# MCU.net
KiCad netlist of a schematic drawn in Altium Designer
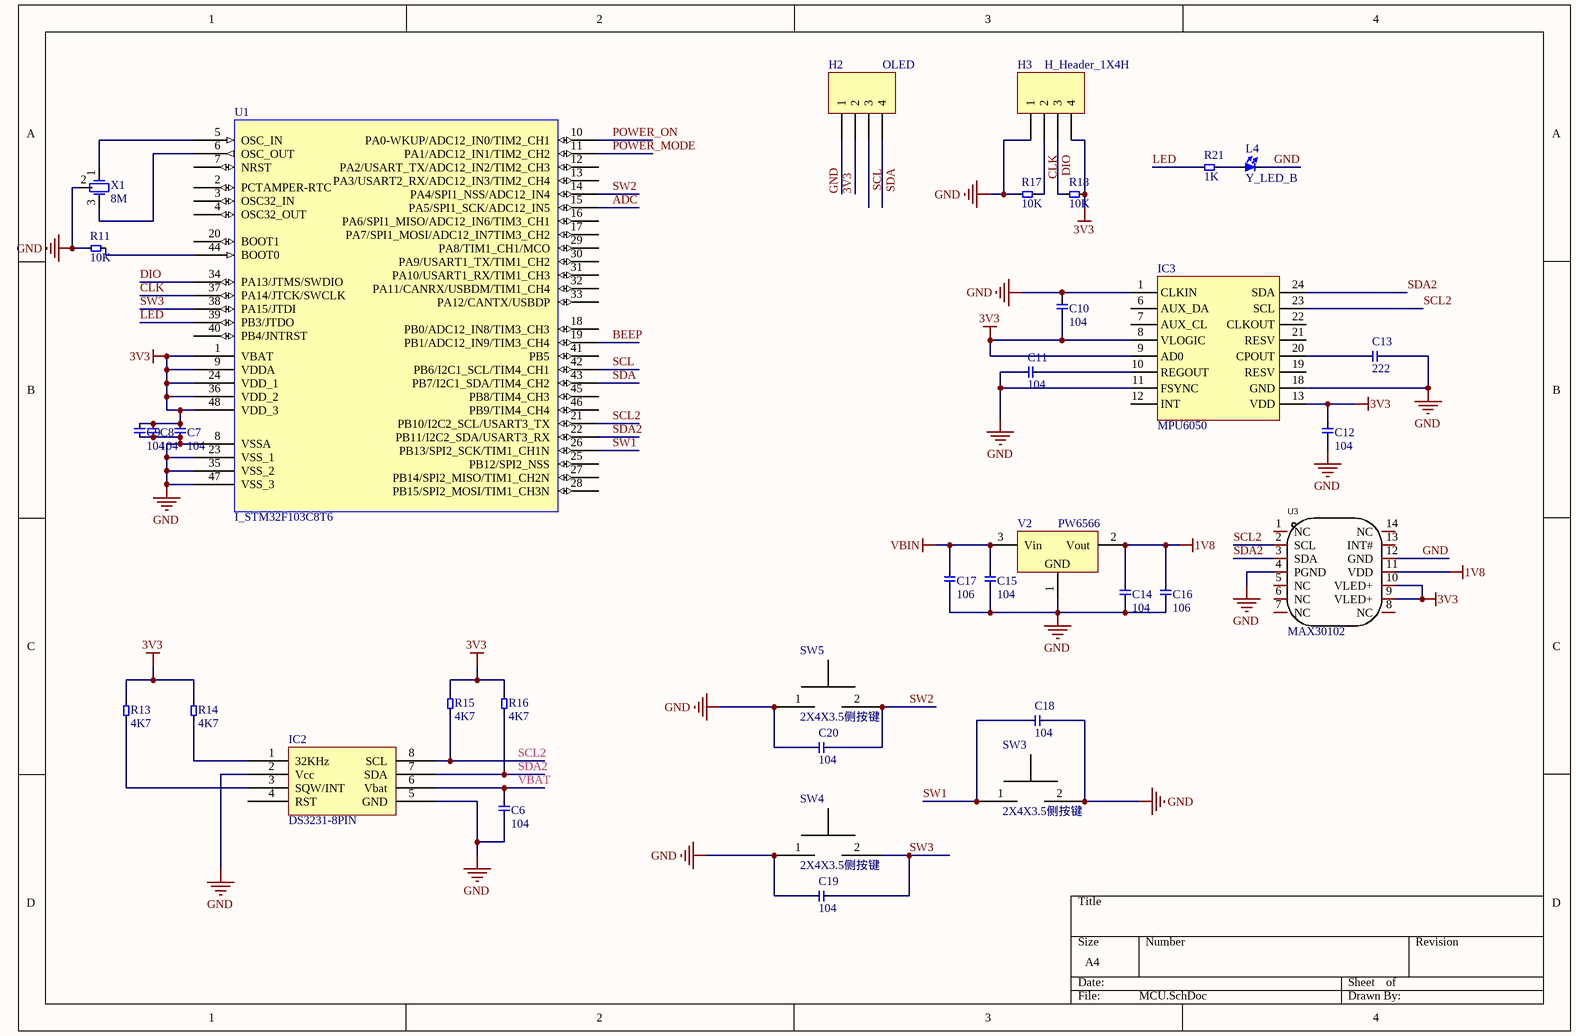
[diagram p0: MCU.SchDoc]

(export (version "E")
  (design (tool "Eeschema 10.0.6"))
  (components
    (comp (ref "C6")
      (value "104")
      (footprint "C_0603")
      (description "无极性贴片电容")
      (libsource (lib "电阻电容电感库") (part "C_无极贴片"))
    )
    (comp (ref "C7")
      (value "104")
      (footprint "C_0603")
      (description "无极性贴片电容")
      (libsource (lib "电阻电容电感库") (part "C_无极贴片"))
    )
    (comp (ref "C8")
      (value "104")
      (footprint "C_0603")
      (description "无极性贴片电容")
      (libsource (lib "电阻电容电感库") (part "C_无极贴片"))
    )
    (comp (ref "C9")
      (value "104")
      (footprint "C_0603")
      (description "无极性贴片电容")
      (libsource (lib "电阻电容电感库") (part "C_无极贴片"))
    )
    (comp (ref "C10")
      (value "104")
      (footprint "C_0603")
      (description "无极性贴片电容")
      (libsource (lib "电阻电容电感库") (part "C_无极贴片"))
    )
    (comp (ref "C11")
      (value "104")
      (footprint "C_0603")
      (description "无极性贴片电容")
      (libsource (lib "电阻电容电感库") (part "C_无极贴片"))
    )
    (comp (ref "C12")
      (value "104")
      (footprint "C_0603")
      (description "无极性贴片电容")
      (libsource (lib "电阻电容电感库") (part "C_无极贴片"))
    )
    (comp (ref "C13")
      (value "222")
      (footprint "C_0603")
      (description "无极性贴片电容")
      (libsource (lib "电阻电容电感库") (part "C_无极贴片"))
    )
    (comp (ref "C14")
      (value "104")
      (footprint "C_0603")
      (description "无极性贴片电容")
      (libsource (lib "电阻电容电感库") (part "C_无极贴片"))
    )
    (comp (ref "C15")
      (value "104")
      (footprint "C_0603")
      (description "无极性贴片电容")
      (libsource (lib "电阻电容电感库") (part "C_无极贴片"))
    )
    (comp (ref "C16")
      (value "106")
      (footprint "C_0603")
      (description "无极性贴片电容")
      (libsource (lib "电阻电容电感库") (part "C_无极贴片"))
    )
    (comp (ref "C17")
      (value "106")
      (footprint "C_0603")
      (description "无极性贴片电容")
      (libsource (lib "电阻电容电感库") (part "C_无极贴片"))
    )
    (comp (ref "C18")
      (value "104")
      (footprint "C_0603")
      (description "无极性贴片电容")
      (libsource (lib "电阻电容电感库") (part "C_无极贴片"))
    )
    (comp (ref "C19")
      (value "104")
      (footprint "C_0603")
      (description "无极性贴片电容")
      (libsource (lib "电阻电容电感库") (part "C_无极贴片"))
    )
    (comp (ref "C20")
      (value "104")
      (footprint "C_0603")
      (description "无极性贴片电容")
      (libsource (lib "电阻电容电感库") (part "C_无极贴片"))
    )
    (comp (ref "H2")
      (value "OLED")
      (footprint "H_Header_1X4")
      (description "单排4针排母")
      (fields (field (name "PUBLISHER") "Altium Limited"))
      (libsource (lib "接插件") (part "H_Header_1X4H"))
    )
    (comp (ref "H3")
      (value "H_Header_1X4H")
      (footprint "H_Header_1X4")
      (description "单排4针排母")
      (fields (field (name "PUBLISHER") "Altium Limited"))
      (libsource (lib "接插件") (part "H_Header_1X4H"))
    )
    (comp (ref "IC2")
      (value "DS3231-8PIN")
      (footprint "SOP8_N")
      (libsource (lib "我的元件") (part "DS3231-8PIN"))
    )
    (comp (ref "IC3")
      (value "MPU6050")
      (footprint "QFN24 4x4_M")
      (description "陀螺仪")
      (libsource (lib "我的元件") (part "MPU6050"))
    )
    (comp (ref "L4")
      (value "Y_LED_B")
      (footprint "Y_LED_0603_B")
      (description "蓝色LED")
      (libsource (lib "声光元件") (part "Y_LED_B"))
    )
    (comp (ref "R11")
      (value "10K")
      (footprint "R_0603")
      (description "贴片电阻")
      (libsource (lib "电阻电容电感库") (part "R_贴片"))
    )
    (comp (ref "R13")
      (value "4K7")
      (footprint "R_0603")
      (description "贴片电阻")
      (libsource (lib "电阻电容电感库") (part "R_贴片"))
    )
    (comp (ref "R14")
      (value "4K7")
      (footprint "R_0603")
      (description "贴片电阻")
      (libsource (lib "电阻电容电感库") (part "R_贴片"))
    )
    (comp (ref "R15")
      (value "4K7")
      (footprint "R_0603")
      (description "贴片电阻")
      (libsource (lib "电阻电容电感库") (part "R_贴片"))
    )
    (comp (ref "R16")
      (value "4K7")
      (footprint "R_0603")
      (description "贴片电阻")
      (libsource (lib "电阻电容电感库") (part "R_贴片"))
    )
    (comp (ref "R17")
      (value "10K")
      (footprint "R_0603")
      (description "贴片电阻")
      (libsource (lib "电阻电容电感库") (part "R_贴片"))
    )
    (comp (ref "R18")
      (value "10K")
      (footprint "R_0603")
      (description "贴片电阻")
      (libsource (lib "电阻电容电感库") (part "R_贴片"))
    )
    (comp (ref "R21")
      (value "1K")
      (footprint "R_0603")
      (description "贴片电阻")
      (libsource (lib "电阻电容电感库") (part "R_贴片"))
    )
    (comp (ref "SW3")
      (value "2X4X3.5侧按键")
      (footprint "2X4X3.5贴片侧按开关")
      (libsource (lib "MyWatch") (part "2X4X3.5侧按键"))
    )
    (comp (ref "SW4")
      (value "2X4X3.5侧按键")
      (footprint "2X4X3.5贴片侧按开关")
      (libsource (lib "MyWatch") (part "2X4X3.5侧按键"))
    )
    (comp (ref "SW5")
      (value "2X4X3.5侧按键")
      (footprint "2X4X3.5贴片侧按开关")
      (libsource (lib "MyWatch") (part "2X4X3.5侧按键"))
    )
    (comp (ref "U1")
      (value "I_STM32F103C8T6")
      (footprint "I_LQFP-48")
      (description "LQFP-48")
      (libsource (lib "集成器件") (part "I_STM32F103C8T6"))
    )
    (comp (ref "U3")
      (value "MAX30102")
      (footprint "OESIP-14_L5.6-W3.3-P0.80-TL")
      (fields (field (name "MANUFACTURER") "MAXIM(美信)") (field (name "MANUFACTURER PART") "MAX30101EFD+T"))
      (libsource (lib "MAX30102") (part "MAX30101EFD+T"))
    )
    (comp (ref "V2")
      (value "PW6566")
      (footprint "SOT23-3N")
      (description "低压差线性稳压芯片")
      (fields (field (name "版权归属") "源创客"))
      (libsource (lib "MyWatch") (part "XC6206P332MR"))
    )
    (comp (ref "X1")
      (value "8M")
      (footprint "XTAL-3.2*1.3MM")
      (description "8~20M-3.2*1.3mm-3P")
      (libsource (lib "物流小车-pcb-树莓派") (part "XTAL-3213-3P"))
    )
  )
  (nets
    (net (code "1") (name "/ADC") (class "Default")
      (node (ref "U1") (pin "15") (pinfunction "PA5/SPI1_SCK/ADC12_IN5_15") (pintype "bidirectional"))
    )
    (net (code "2") (name "/BEEP") (class "Default")
      (node (ref "U1") (pin "19") (pinfunction "PB1/ADC12_IN9/TIM3_CH4_19") (pintype "bidirectional"))
    )
    (net (code "3") (name "/CLK") (class "Default")
      (node (ref "H3") (pin "2") (pinfunction "2_2") (pintype "passive"))
      (node (ref "R17") (pin "2") (pintype "passive"))
      (node (ref "U1") (pin "37") (pinfunction "PA14/JTCK/SWCLK_37") (pintype "bidirectional"))
    )
    (net (code "4") (name "/DIO") (class "Default")
      (node (ref "H3") (pin "3") (pinfunction "3_3") (pintype "passive"))
      (node (ref "R18") (pin "1") (pintype "passive"))
      (node (ref "U1") (pin "34") (pinfunction "PA13/JTMS/SWDIO_34") (pintype "bidirectional"))
    )
    (net (code "5") (name "/LED") (class "Default")
      (node (ref "R21") (pin "2") (pintype "passive"))
      (node (ref "U1") (pin "39") (pinfunction "PB3/JTDO_39") (pintype "bidirectional"))
    )
    (net (code "6") (name "/POWER_MODE") (class "Default")
      (node (ref "U1") (pin "11") (pinfunction "PA1/ADC12_IN1/TIM2_CH2_11") (pintype "bidirectional"))
    )
    (net (code "7") (name "/POWER_ON") (class "Default")
      (node (ref "U1") (pin "10") (pinfunction "PA0-WKUP/ADC12_IN0/TIM2_CH1_10") (pintype "bidirectional"))
    )
    (net (code "8") (name "/SCL") (class "Default")
      (node (ref "H2") (pin "3") (pinfunction "3_3") (pintype "passive"))
      (node (ref "U1") (pin "42") (pinfunction "PB6/I2C1_SCL/TIM4_CH1_42") (pintype "bidirectional"))
    )
    (net (code "9") (name "/SCL2") (class "Default")
      (node (ref "IC2") (pin "8") (pinfunction "SCL_8") (pintype "passive"))
      (node (ref "IC3") (pin "23") (pinfunction "SCL_23") (pintype "passive"))
      (node (ref "R15") (pin "1") (pintype "passive"))
      (node (ref "U1") (pin "21") (pinfunction "PB10/I2C2_SCL/USART3_TX_21") (pintype "bidirectional"))
      (node (ref "U3") (pin "2") (pinfunction "SCL_2") (pintype "passive"))
    )
    (net (code "10") (name "/SDA") (class "Default")
      (node (ref "H2") (pin "4") (pinfunction "4_4") (pintype "passive"))
      (node (ref "U1") (pin "43") (pinfunction "PB7/I2C1_SDA/TIM4_CH2_43") (pintype "bidirectional"))
    )
    (net (code "11") (name "/SDA2") (class "Default")
      (node (ref "IC2") (pin "7") (pinfunction "SDA_7") (pintype "passive"))
      (node (ref "IC3") (pin "24") (pinfunction "SDA_24") (pintype "passive"))
      (node (ref "R16") (pin "1") (pintype "passive"))
      (node (ref "U1") (pin "22") (pinfunction "PB11/I2C2_SDA/USART3_RX_22") (pintype "bidirectional"))
      (node (ref "U3") (pin "3") (pinfunction "SDA_3") (pintype "passive"))
    )
    (net (code "12") (name "/SW1") (class "Default")
      (node (ref "C18") (pin "1") (pinfunction "1_1") (pintype "passive"))
      (node (ref "SW3") (pin "1") (pinfunction "1_1") (pintype "passive"))
      (node (ref "U1") (pin "26") (pinfunction "PB13/SPI2_SCK/TIM1_CH1N_26") (pintype "bidirectional"))
    )
    (net (code "13") (name "/SW2") (class "Default")
      (node (ref "C20") (pin "2") (pinfunction "2_2") (pintype "passive"))
      (node (ref "SW5") (pin "2") (pinfunction "2_2") (pintype "passive"))
      (node (ref "U1") (pin "14") (pinfunction "PA4/SPI1_NSS/ADC12_IN4_14") (pintype "bidirectional"))
    )
    (net (code "14") (name "/SW3") (class "Default")
      (node (ref "C19") (pin "2") (pinfunction "2_2") (pintype "passive"))
      (node (ref "SW4") (pin "2") (pinfunction "2_2") (pintype "passive"))
      (node (ref "U1") (pin "38") (pinfunction "PA15/JTDI_38") (pintype "bidirectional"))
    )
    (net (code "15") (name "/VBAT") (class "Default")
      (node (ref "C6") (pin "2") (pinfunction "2_2") (pintype "passive"))
      (node (ref "IC2") (pin "6") (pinfunction "Vbat_6") (pintype "passive"))
    )
    (net (code "16") (name "1V8") (class "Default")
      (node (ref "C14") (pin "2") (pinfunction "2_2") (pintype "passive"))
      (node (ref "C16") (pin "2") (pinfunction "2_2") (pintype "passive"))
      (node (ref "U3") (pin "11") (pinfunction "VDD_11") (pintype "passive"))
      (node (ref "V2") (pin "2") (pinfunction "Vout_2") (pintype "passive"))
    )
    (net (code "17") (name "3V3") (class "Default")
      (node (ref "C10") (pin "1") (pinfunction "1_1") (pintype "passive"))
      (node (ref "C12") (pin "1") (pinfunction "1_1") (pintype "passive"))
      (node (ref "C7") (pin "2") (pinfunction "2_2") (pintype "passive"))
      (node (ref "C8") (pin "2") (pinfunction "2_2") (pintype "passive"))
      (node (ref "C9") (pin "2") (pinfunction "2_2") (pintype "passive"))
      (node (ref "H2") (pin "2") (pinfunction "2_2") (pintype "passive"))
      (node (ref "H3") (pin "4") (pinfunction "4_4") (pintype "passive"))
      (node (ref "IC3") (pin "13") (pinfunction "VDD_13") (pintype "passive"))
      (node (ref "IC3") (pin "8") (pinfunction "VLOGIC_8") (pintype "passive"))
      (node (ref "IC3") (pin "9") (pinfunction "AD0_9") (pintype "passive"))
      (node (ref "R13") (pin "2") (pintype "passive"))
      (node (ref "R14") (pin "2") (pintype "passive"))
      (node (ref "R15") (pin "2") (pintype "passive"))
      (node (ref "R16") (pin "2") (pintype "passive"))
      (node (ref "R18") (pin "2") (pintype "passive"))
      (node (ref "U1") (pin "1") (pinfunction "VBAT_1") (pintype "power_in"))
      (node (ref "U1") (pin "24") (pinfunction "VDD_1_24") (pintype "power_in"))
      (node (ref "U1") (pin "36") (pinfunction "VDD_2_36") (pintype "power_in"))
      (node (ref "U1") (pin "48") (pinfunction "VDD_3_48") (pintype "power_in"))
      (node (ref "U1") (pin "9") (pinfunction "VDDA_9") (pintype "power_in"))
      (node (ref "U3") (pin "10") (pinfunction "VLED+_10") (pintype "passive"))
      (node (ref "U3") (pin "9") (pinfunction "VLED+_9") (pintype "passive"))
    )
    (net (code "18") (name "GND") (class "Default")
      (node (ref "C10") (pin "2") (pinfunction "2_2") (pintype "passive"))
      (node (ref "C11") (pin "2") (pinfunction "2_2") (pintype "passive"))
      (node (ref "C12") (pin "2") (pinfunction "2_2") (pintype "passive"))
      (node (ref "C13") (pin "2") (pinfunction "2_2") (pintype "passive"))
      (node (ref "C14") (pin "1") (pinfunction "1_1") (pintype "passive"))
      (node (ref "C15") (pin "1") (pinfunction "1_1") (pintype "passive"))
      (node (ref "C16") (pin "1") (pinfunction "1_1") (pintype "passive"))
      (node (ref "C17") (pin "1") (pinfunction "1_1") (pintype "passive"))
      (node (ref "C18") (pin "2") (pinfunction "2_2") (pintype "passive"))
      (node (ref "C19") (pin "1") (pinfunction "1_1") (pintype "passive"))
      (node (ref "C20") (pin "1") (pinfunction "1_1") (pintype "passive"))
      (node (ref "C6") (pin "1") (pinfunction "1_1") (pintype "passive"))
      (node (ref "C7") (pin "1") (pinfunction "1_1") (pintype "passive"))
      (node (ref "C8") (pin "1") (pinfunction "1_1") (pintype "passive"))
      (node (ref "C9") (pin "1") (pinfunction "1_1") (pintype "passive"))
      (node (ref "H2") (pin "1") (pinfunction "1_1") (pintype "passive"))
      (node (ref "H3") (pin "1") (pinfunction "1_1") (pintype "passive"))
      (node (ref "IC2") (pin "2") (pinfunction "Vcc_2") (pintype "passive"))
      (node (ref "IC2") (pin "5") (pinfunction "GND_5") (pintype "passive"))
      (node (ref "IC3") (pin "1") (pinfunction "CLKIN_1") (pintype "passive"))
      (node (ref "IC3") (pin "11") (pinfunction "FSYNC_11") (pintype "passive"))
      (node (ref "IC3") (pin "18") (pinfunction "GND_18") (pintype "passive"))
      (node (ref "L4") (pin "2") (pintype "passive"))
      (node (ref "R11") (pin "1") (pintype "passive"))
      (node (ref "R17") (pin "1") (pintype "passive"))
      (node (ref "SW3") (pin "2") (pinfunction "2_2") (pintype "passive"))
      (node (ref "SW4") (pin "1") (pinfunction "1_1") (pintype "passive"))
      (node (ref "SW5") (pin "1") (pinfunction "1_1") (pintype "passive"))
      (node (ref "U1") (pin "23") (pinfunction "VSS_1_23") (pintype "power_in"))
      (node (ref "U1") (pin "35") (pinfunction "VSS_2_35") (pintype "power_in"))
      (node (ref "U1") (pin "47") (pinfunction "VSS_3_47") (pintype "power_in"))
      (node (ref "U1") (pin "8") (pinfunction "VSSA_8") (pintype "power_in"))
      (node (ref "U3") (pin "12") (pinfunction "GND_12") (pintype "passive"))
      (node (ref "U3") (pin "4") (pinfunction "PGND_4") (pintype "passive"))
      (node (ref "V2") (pin "1") (pinfunction "GND_1") (pintype "passive"))
      (node (ref "X1") (pin "2") (pinfunction "2_2") (pintype "passive"))
    )
    (net (code "19") (name "Net-(IC2-32KHz)") (class "Default")
      (node (ref "IC2") (pin "1") (pinfunction "32KHz_1") (pintype "passive"))
      (node (ref "R14") (pin "1") (pintype "passive"))
    )
    (net (code "20") (name "Net-(IC2-SQW{slash}INT)") (class "Default")
      (node (ref "IC2") (pin "3") (pinfunction "SQW/INT_3") (pintype "passive"))
      (node (ref "R13") (pin "1") (pintype "passive"))
    )
    (net (code "21") (name "Net-(IC3-CPOUT)") (class "Default")
      (node (ref "C13") (pin "1") (pinfunction "1_1") (pintype "passive"))
      (node (ref "IC3") (pin "20") (pinfunction "CPOUT_20") (pintype "passive"))
    )
    (net (code "22") (name "Net-(IC3-REGOUT)") (class "Default")
      (node (ref "C11") (pin "1") (pinfunction "1_1") (pintype "passive"))
      (node (ref "IC3") (pin "10") (pinfunction "REGOUT_10") (pintype "passive"))
    )
    (net (code "23") (name "Net-(L4-Pad1)") (class "Default")
      (node (ref "L4") (pin "1") (pintype "passive"))
      (node (ref "R21") (pin "1") (pintype "passive"))
    )
    (net (code "24") (name "Net-(U1-BOOT0)") (class "Default")
      (node (ref "R11") (pin "2") (pintype "passive"))
      (node (ref "U1") (pin "44") (pinfunction "BOOT0_44") (pintype "input"))
    )
    (net (code "25") (name "Net-(U1-OSC_IN)") (class "Default")
      (node (ref "U1") (pin "5") (pinfunction "OSC_IN_5") (pintype "input"))
      (node (ref "X1") (pin "1") (pinfunction "OSC1_1") (pintype "passive"))
    )
    (net (code "26") (name "Net-(U1-OSC_OUT)") (class "Default")
      (node (ref "U1") (pin "6") (pinfunction "OSC_OUT_6") (pintype "output"))
      (node (ref "X1") (pin "3") (pinfunction "3_3") (pintype "passive"))
    )
    (net (code "27") (name "VBIN") (class "Default")
      (node (ref "C15") (pin "2") (pinfunction "2_2") (pintype "passive"))
      (node (ref "C17") (pin "2") (pinfunction "2_2") (pintype "passive"))
      (node (ref "V2") (pin "3") (pinfunction "Vin_3") (pintype "passive"))
    )
    (net (code "28") (name "unconnected-(IC2-RST-Pad4)") (class "Default")
      (node (ref "IC2") (pin "4") (pinfunction "RST_4") (pintype "passive"))
    )
    (net (code "29") (name "unconnected-(IC3-AUX_CL-Pad7)") (class "Default")
      (node (ref "IC3") (pin "7") (pinfunction "AUX_CL_7") (pintype "passive"))
    )
    (net (code "30") (name "unconnected-(IC3-AUX_DA-Pad6)") (class "Default")
      (node (ref "IC3") (pin "6") (pinfunction "AUX_DA_6") (pintype "passive"))
    )
    (net (code "31") (name "unconnected-(IC3-CLKOUT-Pad22)") (class "Default")
      (node (ref "IC3") (pin "22") (pinfunction "CLKOUT_22") (pintype "passive"))
    )
    (net (code "32") (name "unconnected-(IC3-INT-Pad12)") (class "Default")
      (node (ref "IC3") (pin "12") (pinfunction "INT_12") (pintype "passive"))
    )
    (net (code "33") (name "unconnected-(IC3-RESV-Pad19)") (class "Default")
      (node (ref "IC3") (pin "19") (pinfunction "RESV_19") (pintype "passive"))
    )
    (net (code "34") (name "unconnected-(IC3-RESV-Pad21)") (class "Default")
      (node (ref "IC3") (pin "21") (pinfunction "RESV_21") (pintype "passive"))
    )
    (net (code "35") (name "unconnected-(U1-BOOT1-Pad20)") (class "Default")
      (node (ref "U1") (pin "20") (pinfunction "BOOT1_20") (pintype "bidirectional"))
    )
    (net (code "36") (name "unconnected-(U1-NRST-Pad7)") (class "Default")
      (node (ref "U1") (pin "7") (pinfunction "NRST_7") (pintype "bidirectional"))
    )
    (net (code "37") (name "unconnected-(U1-OSC32_IN-Pad3)") (class "Default")
      (node (ref "U1") (pin "3") (pinfunction "OSC32_IN_3") (pintype "bidirectional"))
    )
    (net (code "38") (name "unconnected-(U1-OSC32_OUT-Pad4)") (class "Default")
      (node (ref "U1") (pin "4") (pinfunction "OSC32_OUT_4") (pintype "bidirectional"))
    )
    (net (code "39") (name "unconnected-(U1-PA2{slash}USART_TX{slash}ADC12_IN2{slash}TIM2_CH3-Pad12)") (class "Default")
      (node (ref "U1") (pin "12") (pinfunction "PA2/USART_TX/ADC12_IN2/TIM2_CH3_12") (pintype "bidirectional"))
    )
    (net (code "40") (name "unconnected-(U1-PA3{slash}USART2_RX{slash}ADC12_IN3{slash}TIM2_CH4-Pad13)") (class "Default")
      (node (ref "U1") (pin "13") (pinfunction "PA3/USART2_RX/ADC12_IN3/TIM2_CH4_13") (pintype "bidirectional"))
    )
    (net (code "41") (name "unconnected-(U1-PA6{slash}SPI1_MISO{slash}ADC12_IN6{slash}TIM3_CH1-Pad16)") (class "Default")
      (node (ref "U1") (pin "16") (pinfunction "PA6/SPI1_MISO/ADC12_IN6/TIM3_CH1_16") (pintype "bidirectional"))
    )
    (net (code "42") (name "unconnected-(U1-PA7{slash}SPI1_MOSI{slash}ADC12_IN7TIM3_CH2-Pad17)") (class "Default")
      (node (ref "U1") (pin "17") (pinfunction "PA7/SPI1_MOSI/ADC12_IN7TIM3_CH2_17") (pintype "bidirectional"))
    )
    (net (code "43") (name "unconnected-(U1-PA8{slash}TIM1_CH1{slash}MCO-Pad29)") (class "Default")
      (node (ref "U1") (pin "29") (pinfunction "PA8/TIM1_CH1/MCO_29") (pintype "bidirectional"))
    )
    (net (code "44") (name "unconnected-(U1-PA9{slash}USART1_TX{slash}TIM1_CH2-Pad30)") (class "Default")
      (node (ref "U1") (pin "30") (pinfunction "PA9/USART1_TX/TIM1_CH2_30") (pintype "bidirectional"))
    )
    (net (code "45") (name "unconnected-(U1-PA10{slash}USART1_RX{slash}TIM1_CH3-Pad31)") (class "Default")
      (node (ref "U1") (pin "31") (pinfunction "PA10/USART1_RX/TIM1_CH3_31") (pintype "bidirectional"))
    )
    (net (code "46") (name "unconnected-(U1-PA11{slash}CANRX{slash}USBDM{slash}TIM1_CH4-Pad32)") (class "Default")
      (node (ref "U1") (pin "32") (pinfunction "PA11/CANRX/USBDM/TIM1_CH4_32") (pintype "bidirectional"))
    )
    (net (code "47") (name "unconnected-(U1-PA12{slash}CANTX{slash}USBDP-Pad33)") (class "Default")
      (node (ref "U1") (pin "33") (pinfunction "PA12/CANTX/USBDP_33") (pintype "bidirectional"))
    )
    (net (code "48") (name "unconnected-(U1-PB0{slash}ADC12_IN8{slash}TIM3_CH3-Pad18)") (class "Default")
      (node (ref "U1") (pin "18") (pinfunction "PB0/ADC12_IN8/TIM3_CH3_18") (pintype "bidirectional"))
    )
    (net (code "49") (name "unconnected-(U1-PB4{slash}JNTRST-Pad40)") (class "Default")
      (node (ref "U1") (pin "40") (pinfunction "PB4/JNTRST_40") (pintype "bidirectional"))
    )
    (net (code "50") (name "unconnected-(U1-PB5-Pad41)") (class "Default")
      (node (ref "U1") (pin "41") (pinfunction "PB5_41") (pintype "bidirectional"))
    )
    (net (code "51") (name "unconnected-(U1-PB8{slash}TIM4_CH3-Pad45)") (class "Default")
      (node (ref "U1") (pin "45") (pinfunction "PB8/TIM4_CH3_45") (pintype "bidirectional"))
    )
    (net (code "52") (name "unconnected-(U1-PB9{slash}TIM4_CH4-Pad46)") (class "Default")
      (node (ref "U1") (pin "46") (pinfunction "PB9/TIM4_CH4_46") (pintype "bidirectional"))
    )
    (net (code "53") (name "unconnected-(U1-PB12{slash}SPI2_NSS-Pad25)") (class "Default")
      (node (ref "U1") (pin "25") (pinfunction "PB12/SPI2_NSS_25") (pintype "bidirectional"))
    )
    (net (code "54") (name "unconnected-(U1-PB14{slash}SPI2_MISO{slash}TIM1_CH2N-Pad27)") (class "Default")
      (node (ref "U1") (pin "27") (pinfunction "PB14/SPI2_MISO/TIM1_CH2N_27") (pintype "bidirectional"))
    )
    (net (code "55") (name "unconnected-(U1-PB15{slash}SPI2_MOSI{slash}TIM1_CH3N-Pad28)") (class "Default")
      (node (ref "U1") (pin "28") (pinfunction "PB15/SPI2_MOSI/TIM1_CH3N_28") (pintype "bidirectional"))
    )
    (net (code "56") (name "unconnected-(U1-PCTAMPER-RTC-Pad2)") (class "Default")
      (node (ref "U1") (pin "2") (pinfunction "PCTAMPER-RTC_2") (pintype "bidirectional"))
    )
    (net (code "57") (name "unconnected-(U3-INT#-Pad13)") (class "Default")
      (node (ref "U3") (pin "13") (pinfunction "INT#_13") (pintype "passive"))
    )
    (net (code "58") (name "unconnected-(U3-NC-Pad1)") (class "Default")
      (node (ref "U3") (pin "1") (pinfunction "NC_1") (pintype "passive"))
    )
    (net (code "59") (name "unconnected-(U3-NC-Pad5)") (class "Default")
      (node (ref "U3") (pin "5") (pinfunction "NC_5") (pintype "passive"))
    )
    (net (code "60") (name "unconnected-(U3-NC-Pad6)") (class "Default")
      (node (ref "U3") (pin "6") (pinfunction "NC_6") (pintype "passive"))
    )
    (net (code "61") (name "unconnected-(U3-NC-Pad7)") (class "Default")
      (node (ref "U3") (pin "7") (pinfunction "NC_7") (pintype "passive"))
    )
    (net (code "62") (name "unconnected-(U3-NC-Pad8)") (class "Default")
      (node (ref "U3") (pin "8") (pinfunction "NC_8") (pintype "passive"))
    )
    (net (code "63") (name "unconnected-(U3-NC-Pad14)") (class "Default")
      (node (ref "U3") (pin "14") (pinfunction "NC_14") (pintype "passive"))
    )
  )
)
